# R650BS1B.net
KiCad netlist of a schematic drawn in EAGLE
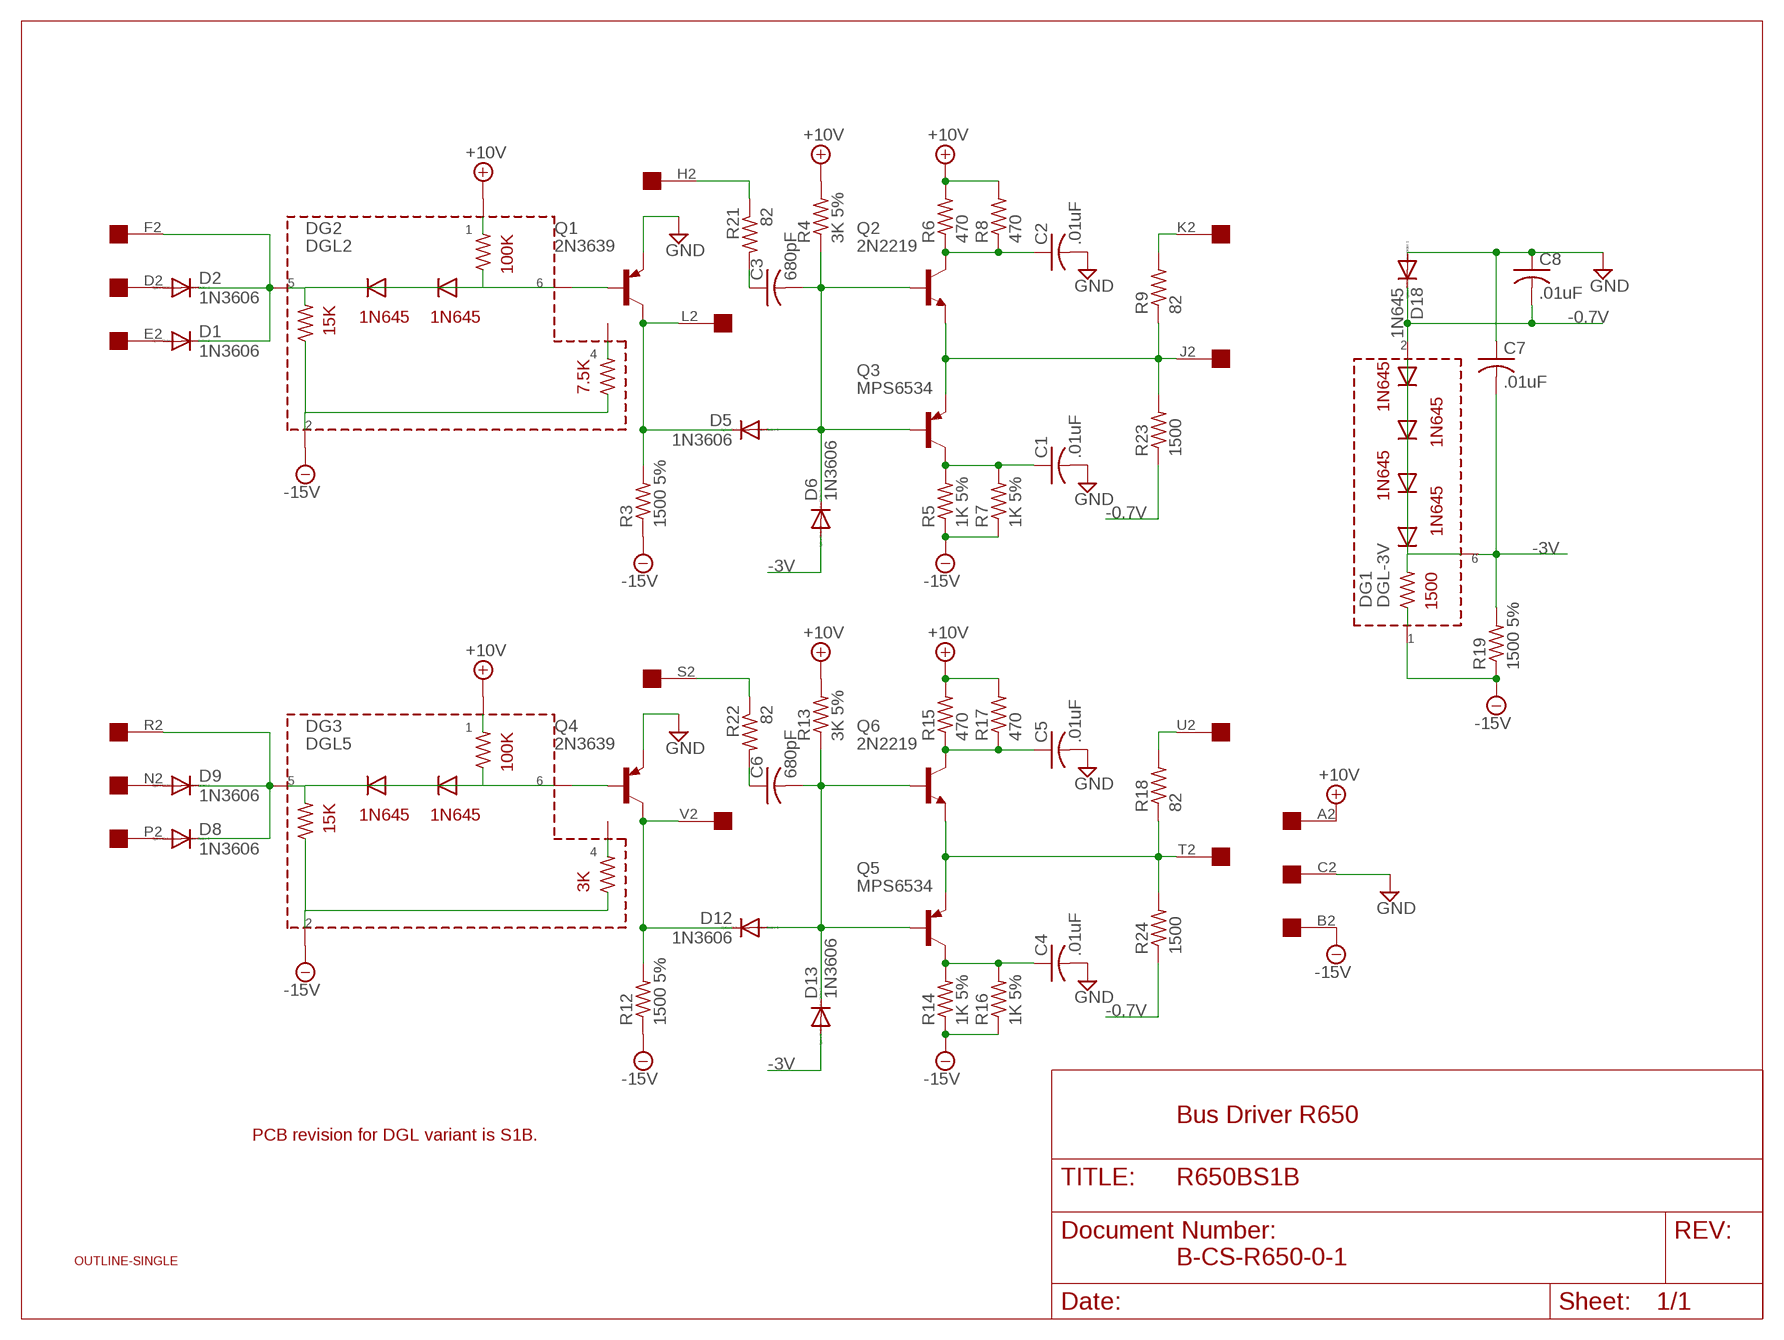
[diagram p0: schematic, sheet 1]

(export (version "E")
  (design (tool "Eeschema 10.0.6"))
  (components
    (comp (ref "C1")
      (value ".01uF")
      (footprint "eagle-import:C102-043X133")
      (libsource (lib "eagle-import") (part "C-US102-043X133"))
    )
    (comp (ref "C2")
      (value ".01uF")
      (footprint "eagle-import:C102-043X133")
      (libsource (lib "eagle-import") (part "C-US102-043X133"))
    )
    (comp (ref "C3")
      (value "680pF")
      (footprint "eagle-import:C102-043X133")
      (libsource (lib "eagle-import") (part "C-US102-043X133"))
    )
    (comp (ref "C4")
      (value ".01uF")
      (footprint "eagle-import:C102-043X133")
      (libsource (lib "eagle-import") (part "C-US102-043X133"))
    )
    (comp (ref "C5")
      (value ".01uF")
      (footprint "eagle-import:C102-043X133")
      (libsource (lib "eagle-import") (part "C-US102-043X133"))
    )
    (comp (ref "C6")
      (value "680pF")
      (footprint "eagle-import:C102-043X133")
      (libsource (lib "eagle-import") (part "C-US102-043X133"))
    )
    (comp (ref "C7")
      (value ".01uF")
      (footprint "eagle-import:C102-043X133")
      (libsource (lib "eagle-import") (part "C-US102-043X133"))
    )
    (comp (ref "C8")
      (value ".01uF")
      (footprint "eagle-import:C102-043X133")
      (libsource (lib "eagle-import") (part "C-US102-043X133"))
    )
    (comp (ref "D1")
      (value "1N3606")
      (footprint "eagle-import:DO35-10")
      (libsource (lib "eagle-import") (part "1N4148DO35-10"))
    )
    (comp (ref "D2")
      (value "1N3606")
      (footprint "eagle-import:DO35-10")
      (libsource (lib "eagle-import") (part "1N4148DO35-10"))
    )
    (comp (ref "D5")
      (value "1N3606")
      (footprint "eagle-import:DO35-10")
      (libsource (lib "eagle-import") (part "1N4148DO35-10"))
    )
    (comp (ref "D6")
      (value "1N3606")
      (footprint "eagle-import:DO35-10")
      (libsource (lib "eagle-import") (part "1N4148DO35-10"))
    )
    (comp (ref "D8")
      (value "1N3606")
      (footprint "eagle-import:DO35-10")
      (libsource (lib "eagle-import") (part "1N4148DO35-10"))
    )
    (comp (ref "D9")
      (value "1N3606")
      (footprint "eagle-import:DO35-10")
      (libsource (lib "eagle-import") (part "1N4148DO35-10"))
    )
    (comp (ref "D12")
      (value "1N3606")
      (footprint "eagle-import:DO35-10")
      (libsource (lib "eagle-import") (part "1N4148DO35-10"))
    )
    (comp (ref "D13")
      (value "1N3606")
      (footprint "eagle-import:DO35-10")
      (libsource (lib "eagle-import") (part "1N4148DO35-10"))
    )
    (comp (ref "D18")
      (value "1N645")
      (footprint "eagle-import:DO35-10")
      (libsource (lib "eagle-import") (part "1N4148DO35-10"))
    )
    (comp (ref "DG1")
      (value "DGL-3V")
      (footprint "eagle-import:DGL2")
      (libsource (lib "eagle-import") (part "DGL-3V"))
    )
    (comp (ref "DG2")
      (value "DGL2")
      (footprint "eagle-import:DGL2")
      (libsource (lib "eagle-import") (part "DGL2"))
    )
    (comp (ref "DG3")
      (value "DGL5")
      (footprint "eagle-import:DGL2")
      (libsource (lib "eagle-import") (part "DGL5"))
    )
    (comp (ref "Q1")
      (value "2N3639")
      (footprint "eagle-import:TO39")
      (libsource (lib "eagle-import") (part "2N3637"))
    )
    (comp (ref "Q2")
      (value "2N2219")
      (footprint "eagle-import:TO5")
      (libsource (lib "eagle-import") (part "2N2219"))
    )
    (comp (ref "Q3")
      (value "MPS6534")
      (footprint "eagle-import:TO39")
      (libsource (lib "eagle-import") (part "2N3637"))
    )
    (comp (ref "Q4")
      (value "2N3639")
      (footprint "eagle-import:TO39")
      (libsource (lib "eagle-import") (part "2N3637"))
    )
    (comp (ref "Q5")
      (value "MPS6534")
      (footprint "eagle-import:TO39")
      (libsource (lib "eagle-import") (part "2N3637"))
    )
    (comp (ref "Q6")
      (value "2N2219")
      (footprint "eagle-import:TO5")
      (libsource (lib "eagle-import") (part "2N2219"))
    )
    (comp (ref "R3")
      (value "1500 5%")
      (footprint "eagle-import:0207_10")
      (libsource (lib "eagle-import") (part "R-US_0207/10"))
    )
    (comp (ref "R4")
      (value "3K 5%")
      (footprint "eagle-import:0207_10")
      (libsource (lib "eagle-import") (part "R-US_0207/10"))
    )
    (comp (ref "R5")
      (value "1K 5%")
      (footprint "eagle-import:0207_10")
      (libsource (lib "eagle-import") (part "R-US_0207/10"))
    )
    (comp (ref "R6")
      (value "470")
      (footprint "eagle-import:0207_10")
      (libsource (lib "eagle-import") (part "R-US_0207/10"))
    )
    (comp (ref "R7")
      (value "1K 5%")
      (footprint "eagle-import:0207_10")
      (libsource (lib "eagle-import") (part "R-US_0207/10"))
    )
    (comp (ref "R8")
      (value "470")
      (footprint "eagle-import:0207_10")
      (libsource (lib "eagle-import") (part "R-US_0207/10"))
    )
    (comp (ref "R9")
      (value "82")
      (footprint "eagle-import:0207_10")
      (libsource (lib "eagle-import") (part "R-US_0207/10"))
    )
    (comp (ref "R12")
      (value "1500 5%")
      (footprint "eagle-import:0207_10")
      (libsource (lib "eagle-import") (part "R-US_0207/10"))
    )
    (comp (ref "R13")
      (value "3K 5%")
      (footprint "eagle-import:0207_10")
      (libsource (lib "eagle-import") (part "R-US_0207/10"))
    )
    (comp (ref "R14")
      (value "1K 5%")
      (footprint "eagle-import:0207_10")
      (libsource (lib "eagle-import") (part "R-US_0207/10"))
    )
    (comp (ref "R15")
      (value "470")
      (footprint "eagle-import:0207_10")
      (libsource (lib "eagle-import") (part "R-US_0207/10"))
    )
    (comp (ref "R16")
      (value "1K 5%")
      (footprint "eagle-import:0207_10")
      (libsource (lib "eagle-import") (part "R-US_0207/10"))
    )
    (comp (ref "R17")
      (value "470")
      (footprint "eagle-import:0207_10")
      (libsource (lib "eagle-import") (part "R-US_0207/10"))
    )
    (comp (ref "R18")
      (value "82")
      (footprint "eagle-import:0207_10")
      (libsource (lib "eagle-import") (part "R-US_0207/10"))
    )
    (comp (ref "R19")
      (value "1500 5%")
      (footprint "eagle-import:0207_10")
      (libsource (lib "eagle-import") (part "R-US_0207/10"))
    )
    (comp (ref "R21")
      (value "82")
      (footprint "eagle-import:0207_10")
      (libsource (lib "eagle-import") (part "R-US_0207/10"))
    )
    (comp (ref "R22")
      (value "82")
      (footprint "eagle-import:0207_10")
      (libsource (lib "eagle-import") (part "R-US_0207/10"))
    )
    (comp (ref "R23")
      (value "1500")
      (footprint "eagle-import:0207_10")
      (libsource (lib "eagle-import") (part "R-US_0207/10"))
    )
    (comp (ref "R24")
      (value "1500")
      (footprint "eagle-import:0207_10")
      (libsource (lib "eagle-import") (part "R-US_0207/10"))
    )
    (comp (ref "U$1")
      (value "OUTLINE-SINGLE")
      (footprint "eagle-import:SINGLE")
      (libsource (lib "eagle-import") (part "OUTLINE-SINGLE"))
    )
    (comp (ref "U$2")
      (value "EDGE-1")
      (footprint "eagle-import:EDGE-CON1")
      (libsource (lib "eagle-import") (part "EDGE-1"))
    )
  )
  (nets
    (net (code "1") (name "+10V") (class "Default")
      (node (ref "DG2") (pin "P$1") (pinfunction "1_P$1") (pintype "passive"))
      (node (ref "DG3") (pin "P$1") (pinfunction "1_P$1") (pintype "passive"))
      (node (ref "R13") (pin "2") (pinfunction "2_2") (pintype "passive"))
      (node (ref "R15") (pin "2") (pinfunction "2_2") (pintype "passive"))
      (node (ref "R17") (pin "2") (pinfunction "2_2") (pintype "passive"))
      (node (ref "R4") (pin "2") (pinfunction "2_2") (pintype "passive"))
      (node (ref "R6") (pin "2") (pinfunction "2_2") (pintype "passive"))
      (node (ref "R8") (pin "2") (pinfunction "2_2") (pintype "passive"))
      (node (ref "U$2") (pin "A2") (pinfunction "1_A2") (pintype "bidirectional"))
    )
    (net (code "2") (name "-15V") (class "Default")
      (node (ref "DG1") (pin "P$1") (pinfunction "1_P$1") (pintype "passive"))
      (node (ref "DG2") (pin "P$2") (pinfunction "2_P$2") (pintype "passive"))
      (node (ref "DG3") (pin "P$2") (pinfunction "2_P$2") (pintype "passive"))
      (node (ref "R12") (pin "1") (pinfunction "1_1") (pintype "passive"))
      (node (ref "R14") (pin "1") (pinfunction "1_1") (pintype "passive"))
      (node (ref "R16") (pin "1") (pinfunction "1_1") (pintype "passive"))
      (node (ref "R19") (pin "1") (pinfunction "1_1") (pintype "passive"))
      (node (ref "R3") (pin "1") (pinfunction "1_1") (pintype "passive"))
      (node (ref "R5") (pin "1") (pinfunction "1_1") (pintype "passive"))
      (node (ref "R7") (pin "1") (pinfunction "1_1") (pintype "passive"))
      (node (ref "U$2") (pin "B2") (pinfunction "1_B2") (pintype "bidirectional"))
    )
    (net (code "3") (name "/-0.7V") (class "Default")
      (node (ref "C8") (pin "2") (pinfunction "2_2") (pintype "passive"))
      (node (ref "D18") (pin "C") (pinfunction "C_C") (pintype "passive"))
      (node (ref "DG1") (pin "P$2") (pinfunction "2_P$2") (pintype "passive"))
      (node (ref "R23") (pin "1") (pinfunction "1_1") (pintype "passive"))
      (node (ref "R24") (pin "1") (pinfunction "1_1") (pintype "passive"))
    )
    (net (code "4") (name "/-3V") (class "Default")
      (node (ref "C7") (pin "2") (pinfunction "2_2") (pintype "passive"))
      (node (ref "D13") (pin "A") (pinfunction "A_A") (pintype "passive"))
      (node (ref "D6") (pin "A") (pinfunction "A_A") (pintype "passive"))
      (node (ref "DG1") (pin "P$6") (pinfunction "6_P$6") (pintype "passive"))
      (node (ref "R19") (pin "2") (pinfunction "2_2") (pintype "passive"))
    )
    (net (code "5") (name "GND") (class "Default")
      (node (ref "C1") (pin "2") (pinfunction "2_2") (pintype "passive"))
      (node (ref "C2") (pin "2") (pinfunction "2_2") (pintype "passive"))
      (node (ref "C4") (pin "2") (pinfunction "2_2") (pintype "passive"))
      (node (ref "C5") (pin "2") (pinfunction "2_2") (pintype "passive"))
      (node (ref "C7") (pin "1") (pinfunction "1_1") (pintype "passive"))
      (node (ref "C8") (pin "1") (pinfunction "1_1") (pintype "passive"))
      (node (ref "D18") (pin "A") (pinfunction "A_A") (pintype "passive"))
      (node (ref "Q1") (pin "1") (pinfunction "E_1") (pintype "passive"))
      (node (ref "Q4") (pin "1") (pinfunction "E_1") (pintype "passive"))
      (node (ref "U$2") (pin "C2") (pinfunction "1_C2") (pintype "bidirectional"))
    )
    (net (code "6") (name "Net-(C3-Pad1)") (class "Default")
      (node (ref "C3") (pin "1") (pinfunction "1_1") (pintype "passive"))
      (node (ref "R21") (pin "2") (pinfunction "2_2") (pintype "passive"))
    )
    (net (code "7") (name "Net-(C6-Pad1)") (class "Default")
      (node (ref "C6") (pin "1") (pinfunction "1_1") (pintype "passive"))
      (node (ref "R22") (pin "2") (pinfunction "2_2") (pintype "passive"))
    )
    (net (code "8") (name "Net-(DG2-5)") (class "Default")
      (node (ref "D1") (pin "C") (pinfunction "C_C") (pintype "passive"))
      (node (ref "D2") (pin "C") (pinfunction "C_C") (pintype "passive"))
      (node (ref "DG2") (pin "P$5") (pinfunction "5_P$5") (pintype "passive"))
      (node (ref "U$2") (pin "F2") (pinfunction "1_F2") (pintype "bidirectional"))
    )
    (net (code "9") (name "Net-(DG2-6)") (class "Default")
      (node (ref "DG2") (pin "P$6") (pinfunction "6_P$6") (pintype "passive"))
      (node (ref "Q1") (pin "2") (pinfunction "B_2") (pintype "passive"))
    )
    (net (code "10") (name "Net-(DG3-5)") (class "Default")
      (node (ref "D8") (pin "C") (pinfunction "C_C") (pintype "passive"))
      (node (ref "D9") (pin "C") (pinfunction "C_C") (pintype "passive"))
      (node (ref "DG3") (pin "P$5") (pinfunction "5_P$5") (pintype "passive"))
      (node (ref "U$2") (pin "R2") (pinfunction "1_R2") (pintype "bidirectional"))
    )
    (net (code "11") (name "Net-(DG3-6)") (class "Default")
      (node (ref "DG3") (pin "P$6") (pinfunction "6_P$6") (pintype "passive"))
      (node (ref "Q4") (pin "2") (pinfunction "B_2") (pintype "passive"))
    )
    (net (code "12") (name "Net-(Q1-C)") (class "Default")
      (node (ref "D5") (pin "C") (pinfunction "C_C") (pintype "passive"))
      (node (ref "Q1") (pin "3") (pinfunction "C_3") (pintype "passive"))
      (node (ref "R3") (pin "2") (pinfunction "2_2") (pintype "passive"))
      (node (ref "U$2") (pin "L2") (pinfunction "1_L2") (pintype "bidirectional"))
    )
    (net (code "13") (name "Net-(Q2-B)") (class "Default")
      (node (ref "C3") (pin "2") (pinfunction "2_2") (pintype "passive"))
      (node (ref "D5") (pin "A") (pinfunction "A_A") (pintype "passive"))
      (node (ref "D6") (pin "C") (pinfunction "C_C") (pintype "passive"))
      (node (ref "Q2") (pin "2") (pinfunction "B_2") (pintype "passive"))
      (node (ref "Q3") (pin "2") (pinfunction "B_2") (pintype "passive"))
      (node (ref "R4") (pin "1") (pinfunction "1_1") (pintype "passive"))
    )
    (net (code "14") (name "Net-(Q2-C)") (class "Default")
      (node (ref "C2") (pin "1") (pinfunction "1_1") (pintype "passive"))
      (node (ref "Q2") (pin "3") (pinfunction "C_3") (pintype "passive"))
      (node (ref "R6") (pin "1") (pinfunction "1_1") (pintype "passive"))
      (node (ref "R8") (pin "1") (pinfunction "1_1") (pintype "passive"))
    )
    (net (code "15") (name "Net-(Q2-E)") (class "Default")
      (node (ref "Q2") (pin "1") (pinfunction "E_1") (pintype "passive"))
      (node (ref "Q3") (pin "1") (pinfunction "E_1") (pintype "passive"))
      (node (ref "R23") (pin "2") (pinfunction "2_2") (pintype "passive"))
      (node (ref "R9") (pin "1") (pinfunction "1_1") (pintype "passive"))
      (node (ref "U$2") (pin "J2") (pinfunction "1_J2") (pintype "bidirectional"))
    )
    (net (code "16") (name "Net-(Q3-C)") (class "Default")
      (node (ref "C1") (pin "1") (pinfunction "1_1") (pintype "passive"))
      (node (ref "Q3") (pin "3") (pinfunction "C_3") (pintype "passive"))
      (node (ref "R5") (pin "2") (pinfunction "2_2") (pintype "passive"))
      (node (ref "R7") (pin "2") (pinfunction "2_2") (pintype "passive"))
    )
    (net (code "17") (name "Net-(Q4-C)") (class "Default")
      (node (ref "D12") (pin "C") (pinfunction "C_C") (pintype "passive"))
      (node (ref "Q4") (pin "3") (pinfunction "C_3") (pintype "passive"))
      (node (ref "R12") (pin "2") (pinfunction "2_2") (pintype "passive"))
      (node (ref "U$2") (pin "V2") (pinfunction "1_V2") (pintype "bidirectional"))
    )
    (net (code "18") (name "Net-(Q5-B)") (class "Default")
      (node (ref "C6") (pin "2") (pinfunction "2_2") (pintype "passive"))
      (node (ref "D12") (pin "A") (pinfunction "A_A") (pintype "passive"))
      (node (ref "D13") (pin "C") (pinfunction "C_C") (pintype "passive"))
      (node (ref "Q5") (pin "2") (pinfunction "B_2") (pintype "passive"))
      (node (ref "Q6") (pin "2") (pinfunction "B_2") (pintype "passive"))
      (node (ref "R13") (pin "1") (pinfunction "1_1") (pintype "passive"))
    )
    (net (code "19") (name "Net-(Q5-C)") (class "Default")
      (node (ref "C4") (pin "1") (pinfunction "1_1") (pintype "passive"))
      (node (ref "Q5") (pin "3") (pinfunction "C_3") (pintype "passive"))
      (node (ref "R14") (pin "2") (pinfunction "2_2") (pintype "passive"))
      (node (ref "R16") (pin "2") (pinfunction "2_2") (pintype "passive"))
    )
    (net (code "20") (name "Net-(Q5-E)") (class "Default")
      (node (ref "Q5") (pin "1") (pinfunction "E_1") (pintype "passive"))
      (node (ref "Q6") (pin "1") (pinfunction "E_1") (pintype "passive"))
      (node (ref "R18") (pin "1") (pinfunction "1_1") (pintype "passive"))
      (node (ref "R24") (pin "2") (pinfunction "2_2") (pintype "passive"))
      (node (ref "U$2") (pin "T2") (pinfunction "1_T2") (pintype "bidirectional"))
    )
    (net (code "21") (name "Net-(Q6-C)") (class "Default")
      (node (ref "C5") (pin "1") (pinfunction "1_1") (pintype "passive"))
      (node (ref "Q6") (pin "3") (pinfunction "C_3") (pintype "passive"))
      (node (ref "R15") (pin "1") (pinfunction "1_1") (pintype "passive"))
      (node (ref "R17") (pin "1") (pinfunction "1_1") (pintype "passive"))
    )
    (net (code "22") (name "Net-(U$2D-1)") (class "Default")
      (node (ref "D2") (pin "A") (pinfunction "A_A") (pintype "passive"))
      (node (ref "U$2") (pin "D2") (pinfunction "1_D2") (pintype "bidirectional"))
    )
    (net (code "23") (name "Net-(U$2E-1)") (class "Default")
      (node (ref "D1") (pin "A") (pinfunction "A_A") (pintype "passive"))
      (node (ref "U$2") (pin "E2") (pinfunction "1_E2") (pintype "bidirectional"))
    )
    (net (code "24") (name "Net-(U$2G-1)") (class "Default")
      (node (ref "R21") (pin "1") (pinfunction "1_1") (pintype "passive"))
      (node (ref "U$2") (pin "H2") (pinfunction "1_H2") (pintype "bidirectional"))
    )
    (net (code "25") (name "Net-(U$2I-1)") (class "Default")
      (node (ref "R9") (pin "2") (pinfunction "2_2") (pintype "passive"))
      (node (ref "U$2") (pin "K2") (pinfunction "1_K2") (pintype "bidirectional"))
    )
    (net (code "26") (name "Net-(U$2L-1)") (class "Default")
      (node (ref "D9") (pin "A") (pinfunction "A_A") (pintype "passive"))
      (node (ref "U$2") (pin "N2") (pinfunction "1_N2") (pintype "bidirectional"))
    )
    (net (code "27") (name "Net-(U$2M-1)") (class "Default")
      (node (ref "D8") (pin "A") (pinfunction "A_A") (pintype "passive"))
      (node (ref "U$2") (pin "P2") (pinfunction "1_P2") (pintype "bidirectional"))
    )
    (net (code "28") (name "Net-(U$2O-1)") (class "Default")
      (node (ref "R22") (pin "1") (pinfunction "1_1") (pintype "passive"))
      (node (ref "U$2") (pin "S2") (pinfunction "1_S2") (pintype "bidirectional"))
    )
    (net (code "29") (name "Net-(U$2Q-1)") (class "Default")
      (node (ref "R18") (pin "2") (pinfunction "2_2") (pintype "passive"))
      (node (ref "U$2") (pin "U2") (pinfunction "1_U2") (pintype "bidirectional"))
    )
    (net (code "30") (name "unconnected-(DG2-4-PadP$4)") (class "Default")
      (node (ref "DG2") (pin "P$4") (pinfunction "4_P$4") (pintype "passive"))
    )
    (net (code "31") (name "unconnected-(DG3-4-PadP$4)") (class "Default")
      (node (ref "DG3") (pin "P$4") (pinfunction "4_P$4") (pintype "passive"))
    )
  )
)
